# Microcontroller.net
KiCad netlist of a schematic drawn in Altium Designer
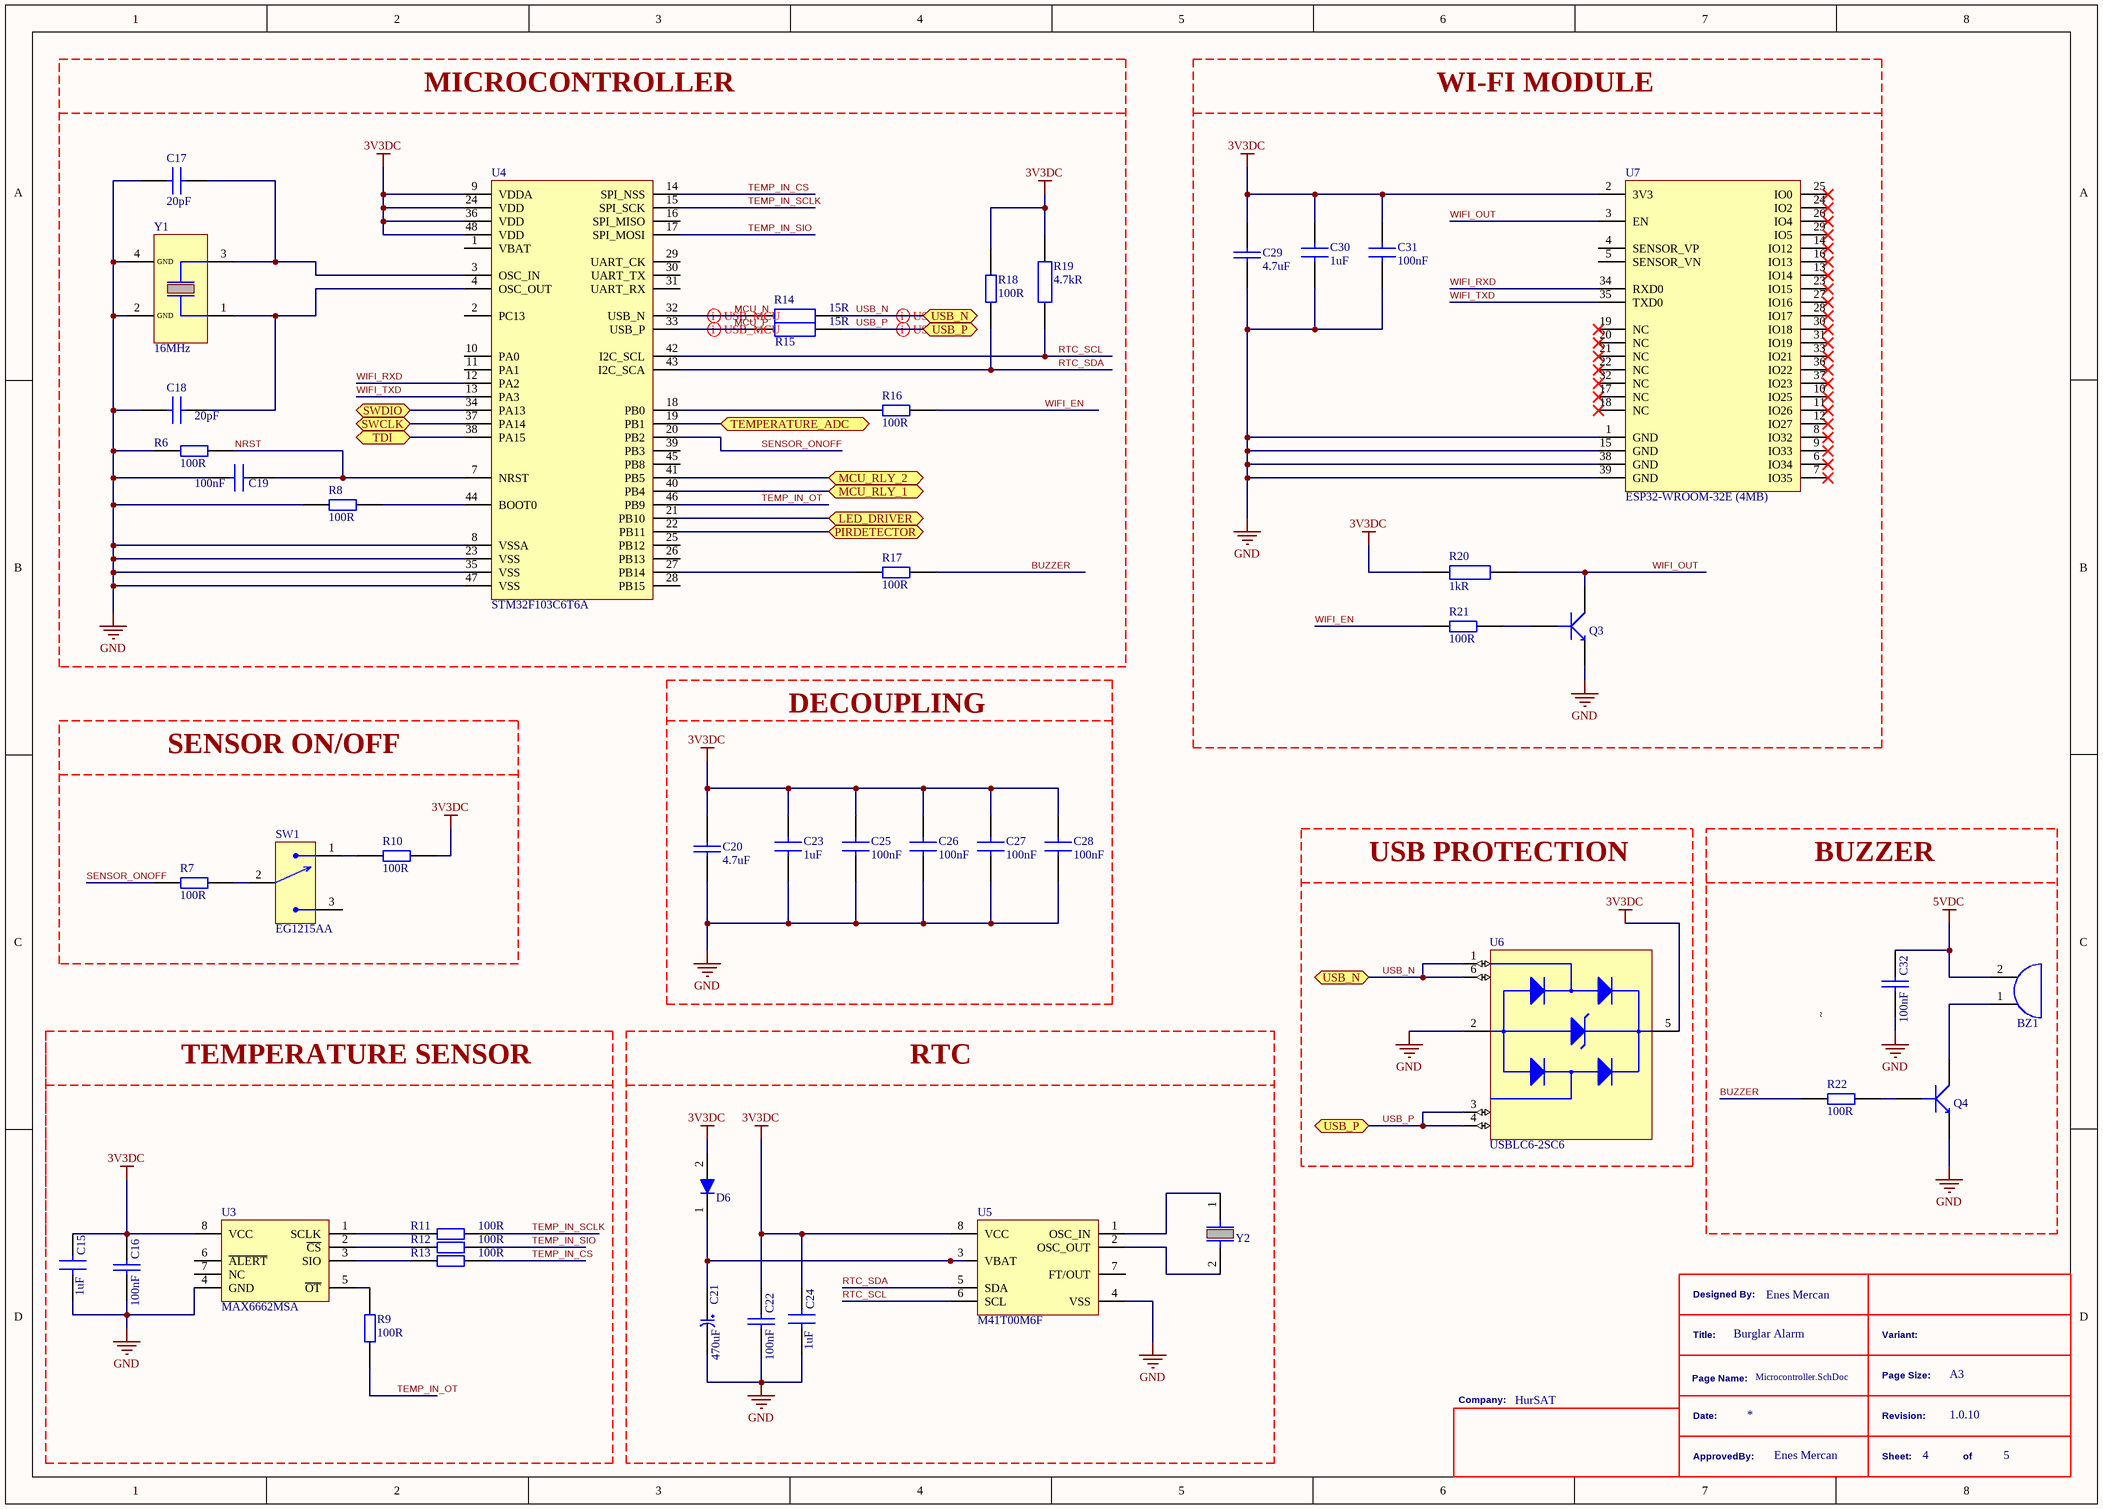
[diagram p0: Microcontroller.SchDoc]

(export (version "E")
  (design (tool "Eeschema 10.0.6"))
  (components
    (comp (ref "BZ1")
      (value "CMI-9605IC-0580T")
      (footprint "CMI-9605IC-0580T")
      (description "Buzzers Indicator, Internally Driven Magnetic 5 V 30mA 2.7kHz 80dB @ 5V, 10cm Through Hole PC Pins")
      (fields (field (name "MANUFACTURER") "CUI Devices") (field (name "DESIGNEDBY") "ENES"))
      (libsource (lib "SecurityBoard") (part "CMI-9605IC-0580T"))
    )
    (comp (ref "C15")
      (value "CL21B105KBFNNNE")
      (footprint "CAP_0805")
      (fields
        (field (name "MANUFACTURER") "Samsung")
        (field (name "TOLERANCE") "10%")
        (field (name "VOLTAGE") "50V")
        (field (name "CAPACITANCE") "1uF")
      )
      (libsource (lib "SecurityBoard") (part "CAP CER 1uF 0805"))
    )
    (comp (ref "C16")
      (value "CL21B104KBCNNNC")
      (footprint "CAP_0805")
      (description "CAP CER %10 0805")
      (fields
        (field (name "MANUFACTURER") "Samsung")
        (field (name "TOLERANCE") "10%")
        (field (name "CAPACITANCE") "100nF")
      )
      (libsource (lib "SecurityBoard") (part "CAP CER 100nF  0805"))
    )
    (comp (ref "C17")
      (value "CL10C200JB8NNNC")
      (footprint "cap_0603")
      (fields
        (field (name "MANUFACTURER") "Samsung")
        (field (name "TOLERANCE") "5%")
        (field (name "VOLTAGE") "50V")
        (field (name "CAPACITANCE") "20pF")
      )
      (libsource (lib "SecurityBoard") (part "CAP CER 20pF"))
    )
    (comp (ref "C18")
      (value "CL10C200JB8NNNC")
      (footprint "cap_0603")
      (fields
        (field (name "MANUFACTURER") "Samsung")
        (field (name "TOLERANCE") "5%")
        (field (name "VOLTAGE") "50V")
        (field (name "CAPACITANCE") "20pF")
      )
      (libsource (lib "SecurityBoard") (part "CAP CER 20pF"))
    )
    (comp (ref "C19")
      (value "C0603X104K4RACTU")
      (footprint "cap_0603")
      (description "CAP CER 0.1UF 16V X7R 0603")
      (fields
        (field (name "MANUFACTURER") "KEMET")
        (field (name "TOLERANCE") "10%")
        (field (name "CAPACITANCE") "100nF")
        (field (name "DESIGNEDBY") "ENES")
      )
      (libsource (lib "SecurityBoard") (part "CAP CER 100nF  0603"))
    )
    (comp (ref "C20")
      (value "CL21A475KAQNNNE")
      (footprint "CAP_0805")
      (description "CAP CER 4.7uF %10 0805")
      (fields
        (field (name "MANUFACTURER") "Samsung")
        (field (name "TOLERANCE") "10%")
        (field (name "CAPACITANCE") "4.7uF")
      )
      (libsource (lib "SecurityBoard") (part "CAP CER 4.7uF 0805"))
    )
    (comp (ref "C21")
      (value "ESY277M050AH4AA")
      (footprint "CAP_RADIAL_D10P5")
      (description "Cap, 470UF, 50V, Alu Elec, Radial")
      (fields
        (field (name "MANUFACTURER") "KEMET")
        (field (name "MANUFACTURER PART NUMBER") "ESH477M050AH4AA")
        (field (name "CAPACITANCE") "470uF")
      )
      (libsource (lib "SecurityBoard") (part "CAP ALU ELEC 470uF"))
    )
    (comp (ref "C22")
      (value "CL21B104KBCNNNC")
      (footprint "CAP_0805")
      (description "CAP CER %10 0805")
      (fields
        (field (name "MANUFACTURER") "Samsung")
        (field (name "TOLERANCE") "10%")
        (field (name "CAPACITANCE") "100nF")
      )
      (libsource (lib "SecurityBoard") (part "CAP CER 100nF  0805"))
    )
    (comp (ref "C23")
      (value "CL21B105KBFNNNE")
      (footprint "CAP_0805")
      (fields
        (field (name "MANUFACTURER") "Samsung")
        (field (name "TOLERANCE") "10%")
        (field (name "VOLTAGE") "50V")
        (field (name "CAPACITANCE") "1uF")
      )
      (libsource (lib "SecurityBoard") (part "CAP CER 1uF 0805"))
    )
    (comp (ref "C24")
      (value "CL21B105KBFNNNE")
      (footprint "CAP_0805")
      (fields
        (field (name "MANUFACTURER") "Samsung")
        (field (name "TOLERANCE") "10%")
        (field (name "VOLTAGE") "50V")
        (field (name "CAPACITANCE") "1uF")
      )
      (libsource (lib "SecurityBoard") (part "CAP CER 1uF 0805"))
    )
    (comp (ref "C25")
      (value "C0603X104K4RACTU")
      (footprint "cap_0603")
      (description "CAP CER 0.1UF 16V X7R 0603")
      (fields
        (field (name "MANUFACTURER") "KEMET")
        (field (name "TOLERANCE") "10%")
        (field (name "CAPACITANCE") "100nF")
        (field (name "DESIGNEDBY") "ENES")
      )
      (libsource (lib "SecurityBoard") (part "CAP CER 100nF  0603"))
    )
    (comp (ref "C26")
      (value "C0603X104K4RACTU")
      (footprint "cap_0603")
      (description "CAP CER 0.1UF 16V X7R 0603")
      (fields
        (field (name "MANUFACTURER") "KEMET")
        (field (name "TOLERANCE") "10%")
        (field (name "CAPACITANCE") "100nF")
        (field (name "DESIGNEDBY") "ENES")
      )
      (libsource (lib "SecurityBoard") (part "CAP CER 100nF  0603"))
    )
    (comp (ref "C27")
      (value "C0603X104K4RACTU")
      (footprint "cap_0603")
      (description "CAP CER 0.1UF 16V X7R 0603")
      (fields
        (field (name "MANUFACTURER") "KEMET")
        (field (name "TOLERANCE") "10%")
        (field (name "CAPACITANCE") "100nF")
        (field (name "DESIGNEDBY") "ENES")
      )
      (libsource (lib "SecurityBoard") (part "CAP CER 100nF  0603"))
    )
    (comp (ref "C28")
      (value "C0603X104K4RACTU")
      (footprint "cap_0603")
      (description "CAP CER 0.1UF 16V X7R 0603")
      (fields
        (field (name "MANUFACTURER") "KEMET")
        (field (name "TOLERANCE") "10%")
        (field (name "CAPACITANCE") "100nF")
        (field (name "DESIGNEDBY") "ENES")
      )
      (libsource (lib "SecurityBoard") (part "CAP CER 100nF  0603"))
    )
    (comp (ref "C29")
      (value "CL21A475KAQNNNE")
      (footprint "CAP_0805")
      (description "CAP CER 4.7uF %10 0805")
      (fields
        (field (name "MANUFACTURER") "Samsung")
        (field (name "TOLERANCE") "10%")
        (field (name "CAPACITANCE") "4.7uF")
      )
      (libsource (lib "SecurityBoard") (part "CAP CER 4.7uF 0805"))
    )
    (comp (ref "C30")
      (value "CL21B105KBFNNNE")
      (footprint "CAP_0805")
      (fields
        (field (name "MANUFACTURER") "Samsung")
        (field (name "TOLERANCE") "10%")
        (field (name "VOLTAGE") "50V")
        (field (name "CAPACITANCE") "1uF")
      )
      (libsource (lib "SecurityBoard") (part "CAP CER 1uF 0805"))
    )
    (comp (ref "C31")
      (value "C0603X104K4RACTU")
      (footprint "cap_0603")
      (description "CAP CER 0.1UF 16V X7R 0603")
      (fields
        (field (name "MANUFACTURER") "KEMET")
        (field (name "TOLERANCE") "10%")
        (field (name "CAPACITANCE") "100nF")
        (field (name "DESIGNEDBY") "ENES")
      )
      (libsource (lib "SecurityBoard") (part "CAP CER 100nF  0603"))
    )
    (comp (ref "C32")
      (value "CL21B104KBCNNNC")
      (footprint "CAP_0805")
      (description "CAP CER %10 0805")
      (fields
        (field (name "MANUFACTURER") "Samsung")
        (field (name "TOLERANCE") "10%")
        (field (name "CAPACITANCE") "100nF")
      )
      (libsource (lib "SecurityBoard") (part "CAP CER 100nF  0805"))
    )
    (comp (ref "D6")
      (value "1N4148WS")
      (footprint "1N4148WS")
      (description "ON SEMICONDUCTOR - 1N4148WS - Small Signal Diode, Single, 75 V, 150 mA, 1 V, 4 ns")
      (fields (field (name "MANUFACTURER") "ON Semiconductor / Fairchild"))
      (libsource (lib "SecurityBoard") (part "1N4148WS"))
    )
    (comp (ref "Q3")
      (value "MMBT3904-7-F")
      (footprint "MMBT3904-7-F")
      (description "Transistor General Purpose BJT NPN 40 Volt 0.2A Automotive 3-Pin SOT-23")
      (fields (field (name "MANUFACTURER") "Diodes Zetex"))
      (libsource (lib "SecurityBoard") (part "MMBT3904-7-F"))
    )
    (comp (ref "Q4")
      (value "MMBT3904-7-F")
      (footprint "MMBT3904-7-F")
      (description "Transistor General Purpose BJT NPN 40 Volt 0.2A Automotive 3-Pin SOT-23")
      (fields (field (name "MANUFACTURER") "Diodes Zetex"))
      (libsource (lib "SecurityBoard") (part "MMBT3904-7-F"))
    )
    (comp (ref "R6")
      (value "RE0603DRE07100RL")
      (footprint "res_0603")
      (description "Chip Resistor Precision Grade Thick Film 0603 100Ohm 0.5% Paper T/R")
      (fields
        (field (name "MANUFACTURER") "Yageo")
        (field (name "TOLERANCE") "0.5%")
        (field (name "RESISTANCE") "100R")
      )
      (libsource (lib "SecurityBoard") (part "RES 100 OHM 0603"))
    )
    (comp (ref "R7")
      (value "RE0603DRE07100RL")
      (footprint "res_0603")
      (description "Chip Resistor Precision Grade Thick Film 0603 100Ohm 0.5% Paper T/R")
      (fields
        (field (name "MANUFACTURER") "Yageo")
        (field (name "TOLERANCE") "0.5%")
        (field (name "RESISTANCE") "100R")
      )
      (libsource (lib "SecurityBoard") (part "RES 100 OHM 0603"))
    )
    (comp (ref "R8")
      (value "RE0603DRE07100RL")
      (footprint "res_0603")
      (description "Chip Resistor Precision Grade Thick Film 0603 100Ohm 0.5% Paper T/R")
      (fields
        (field (name "MANUFACTURER") "Yageo")
        (field (name "TOLERANCE") "0.5%")
        (field (name "RESISTANCE") "100R")
      )
      (libsource (lib "SecurityBoard") (part "RES 100 OHM 0603"))
    )
    (comp (ref "R9")
      (value "RE0603DRE07100RL")
      (footprint "res_0603")
      (description "Chip Resistor Precision Grade Thick Film 0603 100Ohm 0.5% Paper T/R")
      (fields
        (field (name "MANUFACTURER") "Yageo")
        (field (name "TOLERANCE") "0.5%")
        (field (name "RESISTANCE") "100R")
      )
      (libsource (lib "SecurityBoard") (part "RES 100 OHM 0603"))
    )
    (comp (ref "R10")
      (value "RE0603DRE07100RL")
      (footprint "res_0603")
      (description "Chip Resistor Precision Grade Thick Film 0603 100Ohm 0.5% Paper T/R")
      (fields
        (field (name "MANUFACTURER") "Yageo")
        (field (name "TOLERANCE") "0.5%")
        (field (name "RESISTANCE") "100R")
      )
      (libsource (lib "SecurityBoard") (part "RES 100 OHM 0603"))
    )
    (comp (ref "R11")
      (value "RE0603DRE07100RL")
      (footprint "res_0603")
      (description "Chip Resistor Precision Grade Thick Film 0603 100Ohm 0.5% Paper T/R")
      (fields
        (field (name "MANUFACTURER") "Yageo")
        (field (name "TOLERANCE") "0.5%")
        (field (name "RESISTANCE") "100R")
      )
      (libsource (lib "SecurityBoard") (part "RES 100 OHM 0603"))
    )
    (comp (ref "R12")
      (value "RE0603DRE07100RL")
      (footprint "res_0603")
      (description "Chip Resistor Precision Grade Thick Film 0603 100Ohm 0.5% Paper T/R")
      (fields
        (field (name "MANUFACTURER") "Yageo")
        (field (name "TOLERANCE") "0.5%")
        (field (name "RESISTANCE") "100R")
      )
      (libsource (lib "SecurityBoard") (part "RES 100 OHM 0603"))
    )
    (comp (ref "R13")
      (value "RE0603DRE07100RL")
      (footprint "res_0603")
      (description "Chip Resistor Precision Grade Thick Film 0603 100Ohm 0.5% Paper T/R")
      (fields
        (field (name "MANUFACTURER") "Yageo")
        (field (name "TOLERANCE") "0.5%")
        (field (name "RESISTANCE") "100R")
      )
      (libsource (lib "SecurityBoard") (part "RES 100 OHM 0603"))
    )
    (comp (ref "R14")
      (value "RT0603WRE0715RL")
      (footprint "res_0603")
      (description "RES SMD 15 OHM 0.05% 1/10W 0603")
      (fields
        (field (name "MANUFACTURER") "Yageo")
        (field (name "TOLERANCE") "0.05%")
        (field (name "RESISTANCE") "15R")
      )
      (libsource (lib "SecurityBoard") (part "RES 15 OHM 0603"))
    )
    (comp (ref "R15")
      (value "RT0603WRE0715RL")
      (footprint "res_0603")
      (description "RES SMD 15 OHM 0.05% 1/10W 0603")
      (fields
        (field (name "MANUFACTURER") "Yageo")
        (field (name "TOLERANCE") "0.05%")
        (field (name "RESISTANCE") "15R")
      )
      (libsource (lib "SecurityBoard") (part "RES 15 OHM 0603"))
    )
    (comp (ref "R16")
      (value "RE0603DRE07100RL")
      (footprint "res_0603")
      (description "Chip Resistor Precision Grade Thick Film 0603 100Ohm 0.5% Paper T/R")
      (fields
        (field (name "MANUFACTURER") "Yageo")
        (field (name "TOLERANCE") "0.5%")
        (field (name "RESISTANCE") "100R")
      )
      (libsource (lib "SecurityBoard") (part "RES 100 OHM 0603"))
    )
    (comp (ref "R17")
      (value "RE0603DRE07100RL")
      (footprint "res_0603")
      (description "Chip Resistor Precision Grade Thick Film 0603 100Ohm 0.5% Paper T/R")
      (fields
        (field (name "MANUFACTURER") "Yageo")
        (field (name "TOLERANCE") "0.5%")
        (field (name "RESISTANCE") "100R")
      )
      (libsource (lib "SecurityBoard") (part "RES 100 OHM 0603"))
    )
    (comp (ref "R18")
      (value "RE0603DRE07100RL")
      (footprint "res_0603")
      (description "Chip Resistor Precision Grade Thick Film 0603 100Ohm 0.5% Paper T/R")
      (fields
        (field (name "MANUFACTURER") "Yageo")
        (field (name "TOLERANCE") "0.5%")
        (field (name "RESISTANCE") "100R")
      )
      (libsource (lib "SecurityBoard") (part "RES 100 OHM 0603"))
    )
    (comp (ref "R19")
      (value "RT0603BRB074K7L")
      (footprint "res_0603")
      (description "Res Thin Film 0603 4.7K Ohm 0.1% 0.1W(1/10W) ±10ppm/C Molded SMD Paper T/R")
      (fields
        (field (name "MANUFACTURER") "Yageo")
        (field (name "TOLERANCE") "0.1%")
        (field (name "RESISTANCE") "4.7kR")
      )
      (libsource (lib "SecurityBoard") (part "RES 4K7 OHM 0603"))
    )
    (comp (ref "R20")
      (value "AC0603FR-071KL")
      (footprint "res_0603")
      (description "Res Thick Film 0603 1K Ohm 1% 0.1W(1/10W) ±100ppm/C Epoxy Pad SMD Automotive T/R")
      (fields
        (field (name "MANUFACTURER") "Yageo")
        (field (name "TOLERANCE") "1%")
        (field (name "RESISTANCE") "1kR")
      )
      (libsource (lib "SecurityBoard") (part "RES 1K OHM 0603"))
    )
    (comp (ref "R21")
      (value "RE0603DRE07100RL")
      (footprint "res_0603")
      (description "Chip Resistor Precision Grade Thick Film 0603 100Ohm 0.5% Paper T/R")
      (fields
        (field (name "MANUFACTURER") "Yageo")
        (field (name "TOLERANCE") "0.5%")
        (field (name "RESISTANCE") "100R")
      )
      (libsource (lib "SecurityBoard") (part "RES 100 OHM 0603"))
    )
    (comp (ref "R22")
      (value "RE0603DRE07100RL")
      (footprint "res_0603")
      (description "Chip Resistor Precision Grade Thick Film 0603 100Ohm 0.5% Paper T/R")
      (fields
        (field (name "MANUFACTURER") "Yageo")
        (field (name "TOLERANCE") "0.5%")
        (field (name "RESISTANCE") "100R")
      )
      (libsource (lib "SecurityBoard") (part "RES 100 OHM 0603"))
    )
    (comp (ref "SW1")
      (value "EG1215AA")
      (footprint "EG1215AA")
      (description "Slide Switch, SPDT, 0.025A, 24V, SMD")
      (fields
        (field (name "MANUFACTURER") "E-Switch")
        (field (name "TOLERANCE") "4.95%")
        (field (name "DESIGNEDBY") "ENES")
      )
      (libsource (lib "SecurityBoard") (part "EG1215AA"))
    )
    (comp (ref "U3")
      (value "MAX6662MSA")
      (footprint "SOIC8")
      (description "Temp Sensor Digital Serial (3-Wire, SPI) 8-Pin SOIC N Tube")
      (fields (field (name "MANUFACTURER") "Maxim") (field (name "MANUFACTURER PART NUMBER") "MAX6662MSA+"))
      (libsource (lib "SecurityBoard") (part "MAX6662MSA"))
    )
    (comp (ref "U4")
      (value "STM32F103C6T6A")
      (footprint "LQFP-48")
      (description "MCU 32-bit STM32F ARM Cortex M3 RISC 32KB Flash 2.5V/3.3V 48-Pin LQFP Tray")
      (fields (field (name "MANUFACTURER") "STMicroelectronics") (field (name "DESIGNEDBY") "Enes"))
      (libsource (lib "SecurityBoard") (part "STM32F103C6T6A"))
    )
    (comp (ref "U5")
      (value "M41T00M6F")
      (footprint "SOIC8")
      (description "IC RTC CLK/CALENDAR I2C 8-SOIC")
      (fields (field (name "MANUFACTURER") "STMicroelectronics") (field (name "DESIGNEDBY") "ENES"))
      (libsource (lib "SecurityBoard") (part "M41T00M6F"))
    )
    (comp (ref "U6")
      (value "USBLC6-2SC6")
      (footprint "SOT23-6L")
      (description "TVS DIODE 5.25V 17V SOT23-6")
      (fields (field (name "MANUFACTURER") "STMicroelectronics"))
      (libsource (lib "SecurityBoard") (part "TVS - USB Protection"))
    )
    (comp (ref "U7")
      (value "ESP32-WROOM-32E (4MB)")
      (footprint "ESP32-32E")
      (fields
        (field (name "MANUFACTURER") "Espressif Systems")
        (field (name "MANUFACTURER PART NUMBER") "ESP32-WROOM-32E(4MB)")
        (field (name "DESIGNEDBY") "ENES")
      )
      (libsource (lib "SecurityBoard") (part "ESP32-WROOM-32E"))
    )
    (comp (ref "Y1")
      (value "ECS-160-20-30B-TR")
      (footprint "ECS")
      (description "CRYSTAL 16.0000MHZ 20PF SMD")
      (fields
        (field (name "MANUFACTURER") "ECS International")
        (field (name "TOLERANCE") "50ppm")
        (field (name "FREQUENCY") "16MHz")
      )
      (libsource (lib "SecurityBoard") (part "CRYSTAL_16MHZ"))
    )
    (comp (ref "Y2")
      (value "CRYSTAL_32768KHZ")
      (footprint "ABS05")
      (description "ABRACON - ABS05-32.768KHZ-T - Crystal, 32.768 kHz, SMD, 1.6mm x 1mm, 12.5 pF, 20 ppm, ABS05 Series")
      (fields
        (field (name "MANUFACTURER") "ECS International")
        (field (name "MANUFACTURER PART NUMBER") "ECS-160-20-30B-TR")
      )
      (libsource (lib "SecurityBoard") (part "CRYSTAL_32768KHZ"))
    )
  )
  (nets
    (net (code "1") (name "/BUZZER") (class "Default")
      (node (ref "R17") (pin "2") (pinfunction "2_2") (pintype "passive"))
      (node (ref "R22") (pin "1") (pinfunction "1_1") (pintype "passive"))
    )
    (net (code "2") (name "/LED_DRIVER") (class "Default")
      (node (ref "U4") (pin "21") (pinfunction "PB10_21") (pintype "passive"))
    )
    (net (code "3") (name "/MCU_N") (class "Default")
      (node (ref "R14") (pin "1") (pinfunction "1_1") (pintype "passive"))
      (node (ref "U4") (pin "32") (pinfunction "USB_N_32") (pintype "passive"))
    )
    (net (code "4") (name "/MCU_P") (class "Default")
      (node (ref "R15") (pin "1") (pinfunction "1_1") (pintype "passive"))
      (node (ref "U4") (pin "33") (pinfunction "USB_P_33") (pintype "passive"))
    )
    (net (code "5") (name "/MCU_RLY_1") (class "Default")
      (node (ref "U4") (pin "40") (pinfunction "PB4_40") (pintype "passive"))
    )
    (net (code "6") (name "/MCU_RLY_2") (class "Default")
      (node (ref "U4") (pin "41") (pinfunction "PB5_41") (pintype "passive"))
    )
    (net (code "7") (name "/NRST") (class "Default")
      (node (ref "C19") (pin "1") (pinfunction "1_1") (pintype "passive"))
      (node (ref "R6") (pin "2") (pinfunction "2_2") (pintype "passive"))
      (node (ref "U4") (pin "7") (pinfunction "NRST_7") (pintype "passive"))
    )
    (net (code "8") (name "/PIRDETECTOR") (class "Default")
      (node (ref "U4") (pin "22") (pinfunction "PB11_22") (pintype "passive"))
    )
    (net (code "9") (name "/RTC_SCL") (class "Default")
      (node (ref "R19") (pin "1") (pinfunction "1_1") (pintype "passive"))
      (node (ref "U4") (pin "42") (pinfunction "I2C_SCL_42") (pintype "passive"))
      (node (ref "U5") (pin "6") (pinfunction "SCL_6") (pintype "passive"))
    )
    (net (code "10") (name "/RTC_SDA") (class "Default")
      (node (ref "R18") (pin "1") (pinfunction "1_1") (pintype "passive"))
      (node (ref "U4") (pin "43") (pinfunction "I2C_SCA_43") (pintype "passive"))
      (node (ref "U5") (pin "5") (pinfunction "SDA_5") (pintype "passive"))
    )
    (net (code "11") (name "/SENSOR_ONOFF") (class "Default")
      (node (ref "R7") (pin "1") (pinfunction "1_1") (pintype "passive"))
      (node (ref "U4") (pin "20") (pinfunction "PB2_20") (pintype "passive"))
    )
    (net (code "12") (name "/SWCLK") (class "Default")
      (node (ref "U4") (pin "37") (pinfunction "PA14_37") (pintype "passive"))
    )
    (net (code "13") (name "/SWDIO") (class "Default")
      (node (ref "U4") (pin "34") (pinfunction "PA13_34") (pintype "passive"))
    )
    (net (code "14") (name "/TDI") (class "Default")
      (node (ref "U4") (pin "38") (pinfunction "PA15_38") (pintype "passive"))
    )
    (net (code "15") (name "/TEMPERATURE_ADC") (class "Default")
      (node (ref "U4") (pin "19") (pinfunction "PB1_19") (pintype "passive"))
    )
    (net (code "16") (name "/TEMP_IN_CS") (class "Default")
      (node (ref "R13") (pin "2") (pinfunction "2_2") (pintype "passive"))
      (node (ref "U4") (pin "14") (pinfunction "SPI_NSS_14") (pintype "passive"))
    )
    (net (code "17") (name "/TEMP_IN_OT") (class "Default")
      (node (ref "R9") (pin "2") (pinfunction "2_2") (pintype "passive"))
      (node (ref "U4") (pin "46") (pinfunction "PB9_46") (pintype "passive"))
    )
    (net (code "18") (name "/TEMP_IN_SCLK") (class "Default")
      (node (ref "R11") (pin "2") (pinfunction "2_2") (pintype "passive"))
      (node (ref "U4") (pin "15") (pinfunction "SPI_SCK_15") (pintype "passive"))
    )
    (net (code "19") (name "/TEMP_IN_SIO") (class "Default")
      (node (ref "R12") (pin "2") (pinfunction "2_2") (pintype "passive"))
      (node (ref "U4") (pin "17") (pinfunction "SPI_MOSI_17") (pintype "passive"))
    )
    (net (code "20") (name "/USB_N") (class "Default")
      (node (ref "R14") (pin "2") (pinfunction "2_2") (pintype "passive"))
      (node (ref "U6") (pin "1") (pinfunction "I/O1_1") (pintype "bidirectional"))
      (node (ref "U6") (pin "6") (pinfunction "I/O1_6") (pintype "bidirectional"))
    )
    (net (code "21") (name "/USB_P") (class "Default")
      (node (ref "R15") (pin "2") (pinfunction "2_2") (pintype "passive"))
      (node (ref "U6") (pin "3") (pinfunction "I/O2_3") (pintype "bidirectional"))
      (node (ref "U6") (pin "4") (pinfunction "I/O2_4") (pintype "bidirectional"))
    )
    (net (code "22") (name "/WIFI_EN") (class "Default")
      (node (ref "R16") (pin "2") (pinfunction "2_2") (pintype "passive"))
      (node (ref "R21") (pin "1") (pinfunction "1_1") (pintype "passive"))
    )
    (net (code "23") (name "/WIFI_OUT") (class "Default")
      (node (ref "Q3") (pin "C") (pinfunction "C_C") (pintype "passive"))
      (node (ref "R20") (pin "2") (pinfunction "2_2") (pintype "passive"))
      (node (ref "U7") (pin "3") (pinfunction "EN_3") (pintype "passive"))
    )
    (net (code "24") (name "/WIFI_RXD") (class "Default")
      (node (ref "U4") (pin "12") (pinfunction "PA2_12") (pintype "passive"))
      (node (ref "U7") (pin "34") (pinfunction "RXD0_34") (pintype "passive"))
    )
    (net (code "25") (name "/WIFI_TXD") (class "Default")
      (node (ref "U4") (pin "13") (pinfunction "PA3_13") (pintype "passive"))
      (node (ref "U7") (pin "35") (pinfunction "TXD0_35") (pintype "passive"))
    )
    (net (code "26") (name "3V3DC") (class "Default")
      (node (ref "C15") (pin "2") (pinfunction "2_2") (pintype "passive"))
      (node (ref "C16") (pin "2") (pinfunction "2_2") (pintype "passive"))
      (node (ref "C20") (pin "2") (pinfunction "2_2") (pintype "passive"))
      (node (ref "C22") (pin "2") (pinfunction "2_2") (pintype "passive"))
      (node (ref "C23") (pin "2") (pinfunction "2_2") (pintype "passive"))
      (node (ref "C24") (pin "2") (pinfunction "2_2") (pintype "passive"))
      (node (ref "C25") (pin "2") (pinfunction "2_2") (pintype "passive"))
      (node (ref "C26") (pin "2") (pinfunction "2_2") (pintype "passive"))
      (node (ref "C27") (pin "2") (pinfunction "2_2") (pintype "passive"))
      (node (ref "C28") (pin "2") (pinfunction "2_2") (pintype "passive"))
      (node (ref "C29") (pin "2") (pinfunction "2_2") (pintype "passive"))
      (node (ref "C30") (pin "2") (pinfunction "2_2") (pintype "passive"))
      (node (ref "C31") (pin "2") (pinfunction "2_2") (pintype "passive"))
      (node (ref "D6") (pin "2") (pinfunction "2_2") (pintype "passive"))
      (node (ref "R10") (pin "2") (pinfunction "2_2") (pintype "passive"))
      (node (ref "R18") (pin "2") (pinfunction "2_2") (pintype "passive"))
      (node (ref "R19") (pin "2") (pinfunction "2_2") (pintype "passive"))
      (node (ref "R20") (pin "1") (pinfunction "1_1") (pintype "passive"))
      (node (ref "U3") (pin "8") (pinfunction "VCC_8") (pintype "passive"))
      (node (ref "U4") (pin "24") (pinfunction "VDD_24") (pintype "passive"))
      (node (ref "U4") (pin "36") (pinfunction "VDD_36") (pintype "passive"))
      (node (ref "U4") (pin "48") (pinfunction "VDD_48") (pintype "passive"))
      (node (ref "U4") (pin "9") (pinfunction "VDDA_9") (pintype "passive"))
      (node (ref "U5") (pin "8") (pinfunction "VCC_8") (pintype "passive"))
      (node (ref "U6") (pin "5") (pinfunction "VBUS_5") (pintype "power_in"))
      (node (ref "U7") (pin "2") (pinfunction "3V3_2") (pintype "passive"))
    )
    (net (code "27") (name "5VDC") (class "Default")
      (node (ref "BZ1") (pin "2") (pinfunction "2_2") (pintype "passive"))
      (node (ref "C32") (pin "2") (pinfunction "2_2") (pintype "passive"))
    )
    (net (code "28") (name "GND") (class "Default")
      (node (ref "C15") (pin "1") (pinfunction "1_1") (pintype "passive"))
      (node (ref "C16") (pin "1") (pinfunction "1_1") (pintype "passive"))
      (node (ref "C17") (pin "1") (pinfunction "1_1") (pintype "passive"))
      (node (ref "C18") (pin "1") (pinfunction "1_1") (pintype "passive"))
      (node (ref "C19") (pin "2") (pinfunction "2_2") (pintype "passive"))
      (node (ref "C20") (pin "1") (pinfunction "1_1") (pintype "passive"))
      (node (ref "C21") (pin "2") (pinfunction "2_2") (pintype "passive"))
      (node (ref "C22") (pin "1") (pinfunction "1_1") (pintype "passive"))
      (node (ref "C23") (pin "1") (pinfunction "1_1") (pintype "passive"))
      (node (ref "C24") (pin "1") (pinfunction "1_1") (pintype "passive"))
      (node (ref "C25") (pin "1") (pinfunction "1_1") (pintype "passive"))
      (node (ref "C26") (pin "1") (pinfunction "1_1") (pintype "passive"))
      (node (ref "C27") (pin "1") (pinfunction "1_1") (pintype "passive"))
      (node (ref "C28") (pin "1") (pinfunction "1_1") (pintype "passive"))
      (node (ref "C29") (pin "1") (pinfunction "1_1") (pintype "passive"))
      (node (ref "C30") (pin "1") (pinfunction "1_1") (pintype "passive"))
      (node (ref "C31") (pin "1") (pinfunction "1_1") (pintype "passive"))
      (node (ref "C32") (pin "1") (pinfunction "1_1") (pintype "passive"))
      (node (ref "Q3") (pin "E") (pinfunction "E_E") (pintype "passive"))
      (node (ref "Q4") (pin "E") (pinfunction "E_E") (pintype "passive"))
      (node (ref "R6") (pin "1") (pinfunction "1_1") (pintype "passive"))
      (node (ref "R8") (pin "1") (pinfunction "1_1") (pintype "passive"))
      (node (ref "U3") (pin "4") (pinfunction "GND_4") (pintype "passive"))
      (node (ref "U4") (pin "23") (pinfunction "VSS_23") (pintype "passive"))
      (node (ref "U4") (pin "35") (pinfunction "VSS_35") (pintype "passive"))
      (node (ref "U4") (pin "47") (pinfunction "VSS_47") (pintype "passive"))
      (node (ref "U4") (pin "8") (pinfunction "VSSA_8") (pintype "passive"))
      (node (ref "U5") (pin "4") (pinfunction "VSS_4") (pintype "passive"))
      (node (ref "U6") (pin "2") (pinfunction "GND_2") (pintype "power_in"))
      (node (ref "U7") (pin "1") (pinfunction "GND_1") (pintype "passive"))
      (node (ref "U7") (pin "15") (pinfunction "GND_15") (pintype "passive"))
      (node (ref "U7") (pin "38") (pinfunction "GND_38") (pintype "passive"))
      (node (ref "U7") (pin "39") (pinfunction "GND_39") (pintype "passive"))
      (node (ref "Y1") (pin "2") (pinfunction "GND_2") (pintype "passive"))
      (node (ref "Y1") (pin "4") (pinfunction "GND_4") (pintype "passive"))
    )
    (net (code "29") (name "Net-(BZ1-Pad1)") (class "Default")
      (node (ref "BZ1") (pin "1") (pinfunction "1_1") (pintype "passive"))
      (node (ref "Q4") (pin "C") (pinfunction "C_C") (pintype "passive"))
    )
    (net (code "30") (name "Net-(Q3-PadB)") (class "Default")
      (node (ref "Q3") (pin "B") (pinfunction "B_B") (pintype "passive"))
      (node (ref "R21") (pin "2") (pinfunction "2_2") (pintype "passive"))
    )
    (net (code "31") (name "Net-(Q4-PadB)") (class "Default")
      (node (ref "Q4") (pin "B") (pinfunction "B_B") (pintype "passive"))
      (node (ref "R22") (pin "2") (pinfunction "2_2") (pintype "passive"))
    )
    (net (code "32") (name "Net-(R7-Pad2)") (class "Default")
      (node (ref "R7") (pin "2") (pinfunction "2_2") (pintype "passive"))
      (node (ref "SW1") (pin "2") (pinfunction "2_2") (pintype "passive"))
    )
    (net (code "33") (name "Net-(R10-Pad1)") (class "Default")
      (node (ref "R10") (pin "1") (pinfunction "1_1") (pintype "passive"))
      (node (ref "SW1") (pin "1") (pinfunction "1_1") (pintype "passive"))
    )
    (net (code "34") (name "Net-(U3-SCLK)") (class "Default")
      (node (ref "R11") (pin "1") (pinfunction "1_1") (pintype "passive"))
      (node (ref "U3") (pin "1") (pinfunction "SCLK_1") (pintype "passive"))
    )
    (net (code "35") (name "Net-(U3-SIO)") (class "Default")
      (node (ref "R13") (pin "1") (pinfunction "1_1") (pintype "passive"))
      (node (ref "U3") (pin "3") (pinfunction "SIO_3") (pintype "passive"))
    )
    (net (code "36") (name "Net-(U3-~{CS})") (class "Default")
      (node (ref "R12") (pin "1") (pinfunction "1_1") (pintype "passive"))
      (node (ref "U3") (pin "2") (pinfunction "~{CS}_2") (pintype "passive"))
    )
    (net (code "37") (name "Net-(U3-~{OT})") (class "Default")
      (node (ref "R9") (pin "1") (pinfunction "1_1") (pintype "passive"))
      (node (ref "U3") (pin "5") (pinfunction "~{OT}_5") (pintype "passive"))
    )
    (net (code "38") (name "Net-(U4-BOOT0)") (class "Default")
      (node (ref "R8") (pin "2") (pinfunction "2_2") (pintype "passive"))
      (node (ref "U4") (pin "44") (pinfunction "BOOT0_44") (pintype "passive"))
    )
    (net (code "39") (name "Net-(U4-OSC_IN)") (class "Default")
      (node (ref "C17") (pin "2") (pinfunction "2_2") (pintype "passive"))
      (node (ref "U4") (pin "3") (pinfunction "OSC_IN_3") (pintype "passive"))
      (node (ref "Y1") (pin "3") (pinfunction "3_3") (pintype "passive"))
    )
    (net (code "40") (name "Net-(U4-OSC_OUT)") (class "Default")
      (node (ref "C18") (pin "2") (pinfunction "2_2") (pintype "passive"))
      (node (ref "U4") (pin "4") (pinfunction "OSC_OUT_4") (pintype "passive"))
      (node (ref "Y1") (pin "1") (pinfunction "1_1") (pintype "passive"))
    )
    (net (code "41") (name "Net-(U4-PB0)") (class "Default")
      (node (ref "R16") (pin "1") (pinfunction "1_1") (pintype "passive"))
      (node (ref "U4") (pin "18") (pinfunction "PB0_18") (pintype "passive"))
    )
    (net (code "42") (name "Net-(U4-PB14)") (class "Default")
      (node (ref "R17") (pin "1") (pinfunction "1_1") (pintype "passive"))
      (node (ref "U4") (pin "27") (pinfunction "PB14_27") (pintype "passive"))
    )
    (net (code "43") (name "Net-(U5-OSC_IN)") (class "Default")
      (node (ref "U5") (pin "1") (pinfunction "OSC_IN_1") (pintype "passive"))
      (node (ref "Y2") (pin "1") (pinfunction "1_1") (pintype "passive"))
    )
    (net (code "44") (name "Net-(U5-OSC_OUT)") (class "Default")
      (node (ref "U5") (pin "2") (pinfunction "OSC_OUT_2") (pintype "passive"))
      (node (ref "Y2") (pin "2") (pinfunction "2_2") (pintype "passive"))
    )
    (net (code "45") (name "Net-(U5-VBAT)") (class "Default")
      (node (ref "C21") (pin "1") (pinfunction "1_1") (pintype "passive"))
      (node (ref "D6") (pin "1") (pinfunction "1_1") (pintype "passive"))
      (node (ref "U5") (pin "3") (pinfunction "VBAT_3") (pintype "passive"))
    )
    (net (code "46") (name "unconnected-(SW1-Pad3)") (class "Default")
      (node (ref "SW1") (pin "3") (pinfunction "3_3") (pintype "passive"))
    )
    (net (code "47") (name "unconnected-(U3-NC-Pad7)") (class "Default")
      (node (ref "U3") (pin "7") (pinfunction "NC_7") (pintype "passive"))
    )
    (net (code "48") (name "unconnected-(U3-~{ALERT}-Pad6)") (class "Default")
      (node (ref "U3") (pin "6") (pinfunction "~{ALERT}_6") (pintype "passive"))
    )
    (net (code "49") (name "unconnected-(U4-PA0-Pad10)") (class "Default")
      (node (ref "U4") (pin "10") (pinfunction "PA0_10") (pintype "passive"))
    )
    (net (code "50") (name "unconnected-(U4-PA1-Pad11)") (class "Default")
      (node (ref "U4") (pin "11") (pinfunction "PA1_11") (pintype "passive"))
    )
    (net (code "51") (name "unconnected-(U4-PB3-Pad39)") (class "Default")
      (node (ref "U4") (pin "39") (pinfunction "PB3_39") (pintype "passive"))
    )
    (net (code "52") (name "unconnected-(U4-PB8-Pad45)") (class "Default")
      (node (ref "U4") (pin "45") (pinfunction "PB8_45") (pintype "passive"))
    )
    (net (code "53") (name "unconnected-(U4-PB12-Pad25)") (class "Default")
      (node (ref "U4") (pin "25") (pinfunction "PB12_25") (pintype "passive"))
    )
    (net (code "54") (name "unconnected-(U4-PB13-Pad26)") (class "Default")
      (node (ref "U4") (pin "26") (pinfunction "PB13_26") (pintype "passive"))
    )
    (net (code "55") (name "unconnected-(U4-PB15-Pad28)") (class "Default")
      (node (ref "U4") (pin "28") (pinfunction "PB15_28") (pintype "passive"))
    )
    (net (code "56") (name "unconnected-(U4-PC13-Pad2)") (class "Default")
      (node (ref "U4") (pin "2") (pinfunction "PC13_2") (pintype "passive"))
    )
    (net (code "57") (name "unconnected-(U4-SPI_MISO-Pad16)") (class "Default")
      (node (ref "U4") (pin "16") (pinfunction "SPI_MISO_16") (pintype "passive"))
    )
    (net (code "58") (name "unconnected-(U4-UART_CK-Pad29)") (class "Default")
      (node (ref "U4") (pin "29") (pinfunction "UART_CK_29") (pintype "passive"))
    )
    (net (code "59") (name "unconnected-(U4-UART_RX-Pad31)") (class "Default")
      (node (ref "U4") (pin "31") (pinfunction "UART_RX_31") (pintype "passive"))
    )
    (net (code "60") (name "unconnected-(U4-UART_TX-Pad30)") (class "Default")
      (node (ref "U4") (pin "30") (pinfunction "UART_TX_30") (pintype "passive"))
    )
    (net (code "61") (name "unconnected-(U4-VBAT-Pad1)") (class "Default")
      (node (ref "U4") (pin "1") (pinfunction "VBAT_1") (pintype "passive"))
    )
    (net (code "62") (name "unconnected-(U5-FT{slash}OUT-Pad7)") (class "Default")
      (node (ref "U5") (pin "7") (pinfunction "FT/OUT_7") (pintype "passive"))
    )
    (net (code "63") (name "unconnected-(U7-IO0-Pad25)") (class "Default")
      (node (ref "U7") (pin "25") (pinfunction "IO0_25") (pintype "passive+no_connect"))
    )
    (net (code "64") (name "unconnected-(U7-IO2-Pad24)") (class "Default")
      (node (ref "U7") (pin "24") (pinfunction "IO2_24") (pintype "passive+no_connect"))
    )
    (net (code "65") (name "unconnected-(U7-IO4-Pad26)") (class "Default")
      (node (ref "U7") (pin "26") (pinfunction "IO4_26") (pintype "passive+no_connect"))
    )
    (net (code "66") (name "unconnected-(U7-IO5-Pad29)") (class "Default")
      (node (ref "U7") (pin "29") (pinfunction "IO5_29") (pintype "passive+no_connect"))
    )
    (net (code "67") (name "unconnected-(U7-IO12-Pad14)") (class "Default")
      (node (ref "U7") (pin "14") (pinfunction "IO12_14") (pintype "passive+no_connect"))
    )
    (net (code "68") (name "unconnected-(U7-IO13-Pad16)") (class "Default")
      (node (ref "U7") (pin "16") (pinfunction "IO13_16") (pintype "passive+no_connect"))
    )
    (net (code "69") (name "unconnected-(U7-IO14-Pad13)") (class "Default")
      (node (ref "U7") (pin "13") (pinfunction "IO14_13") (pintype "passive+no_connect"))
    )
    (net (code "70") (name "unconnected-(U7-IO15-Pad23)") (class "Default")
      (node (ref "U7") (pin "23") (pinfunction "IO15_23") (pintype "passive+no_connect"))
    )
    (net (code "71") (name "unconnected-(U7-IO16-Pad27)") (class "Default")
      (node (ref "U7") (pin "27") (pinfunction "IO16_27") (pintype "passive+no_connect"))
    )
    (net (code "72") (name "unconnected-(U7-IO17-Pad28)") (class "Default")
      (node (ref "U7") (pin "28") (pinfunction "IO17_28") (pintype "passive+no_connect"))
    )
    (net (code "73") (name "unconnected-(U7-IO18-Pad30)") (class "Default")
      (node (ref "U7") (pin "30") (pinfunction "IO18_30") (pintype "passive+no_connect"))
    )
    (net (code "74") (name "unconnected-(U7-IO19-Pad31)") (class "Default")
      (node (ref "U7") (pin "31") (pinfunction "IO19_31") (pintype "passive+no_connect"))
    )
    (net (code "75") (name "unconnected-(U7-IO21-Pad33)") (class "Default")
      (node (ref "U7") (pin "33") (pinfunction "IO21_33") (pintype "passive+no_connect"))
    )
    (net (code "76") (name "unconnected-(U7-IO22-Pad36)") (class "Default")
      (node (ref "U7") (pin "36") (pinfunction "IO22_36") (pintype "passive+no_connect"))
    )
    (net (code "77") (name "unconnected-(U7-IO23-Pad37)") (class "Default")
      (node (ref "U7") (pin "37") (pinfunction "IO23_37") (pintype "passive+no_connect"))
    )
    (net (code "78") (name "unconnected-(U7-IO25-Pad10)") (class "Default")
      (node (ref "U7") (pin "10") (pinfunction "IO25_10") (pintype "passive+no_connect"))
    )
    (net (code "79") (name "unconnected-(U7-IO26-Pad11)") (class "Default")
      (node (ref "U7") (pin "11") (pinfunction "IO26_11") (pintype "passive+no_connect"))
    )
    (net (code "80") (name "unconnected-(U7-IO27-Pad12)") (class "Default")
      (node (ref "U7") (pin "12") (pinfunction "IO27_12") (pintype "passive+no_connect"))
    )
    (net (code "81") (name "unconnected-(U7-IO32-Pad8)") (class "Default")
      (node (ref "U7") (pin "8") (pinfunction "IO32_8") (pintype "passive+no_connect"))
    )
    (net (code "82") (name "unconnected-(U7-IO33-Pad9)") (class "Default")
      (node (ref "U7") (pin "9") (pinfunction "IO33_9") (pintype "passive+no_connect"))
    )
    (net (code "83") (name "unconnected-(U7-IO34-Pad6)") (class "Default")
      (node (ref "U7") (pin "6") (pinfunction "IO34_6") (pintype "passive+no_connect"))
    )
    (net (code "84") (name "unconnected-(U7-IO35-Pad7)") (class "Default")
      (node (ref "U7") (pin "7") (pinfunction "IO35_7") (pintype "passive+no_connect"))
    )
    (net (code "85") (name "unconnected-(U7-NC-Pad17)") (class "Default")
      (node (ref "U7") (pin "17") (pinfunction "NC_17") (pintype "passive+no_connect"))
    )
    (net (code "86") (name "unconnected-(U7-NC-Pad18)") (class "Default")
      (node (ref "U7") (pin "18") (pinfunction "NC_18") (pintype "passive+no_connect"))
    )
    (net (code "87") (name "unconnected-(U7-NC-Pad19)") (class "Default")
      (node (ref "U7") (pin "19") (pinfunction "NC_19") (pintype "passive+no_connect"))
    )
    (net (code "88") (name "unconnected-(U7-NC-Pad20)") (class "Default")
      (node (ref "U7") (pin "20") (pinfunction "NC_20") (pintype "passive+no_connect"))
    )
    (net (code "89") (name "unconnected-(U7-NC-Pad21)") (class "Default")
      (node (ref "U7") (pin "21") (pinfunction "NC_21") (pintype "passive+no_connect"))
    )
    (net (code "90") (name "unconnected-(U7-NC-Pad22)") (class "Default")
      (node (ref "U7") (pin "22") (pinfunction "NC_22") (pintype "passive+no_connect"))
    )
    (net (code "91") (name "unconnected-(U7-NC-Pad32)") (class "Default")
      (node (ref "U7") (pin "32") (pinfunction "NC_32") (pintype "passive+no_connect"))
    )
    (net (code "92") (name "unconnected-(U7-SENSOR_VN-Pad5)") (class "Default")
      (node (ref "U7") (pin "5") (pinfunction "SENSOR_VN_5") (pintype "passive"))
    )
    (net (code "93") (name "unconnected-(U7-SENSOR_VP-Pad4)") (class "Default")
      (node (ref "U7") (pin "4") (pinfunction "SENSOR_VP_4") (pintype "passive"))
    )
  )
)
